# smps_schematic.net
KiCad netlist of a schematic drawn in EAGLE
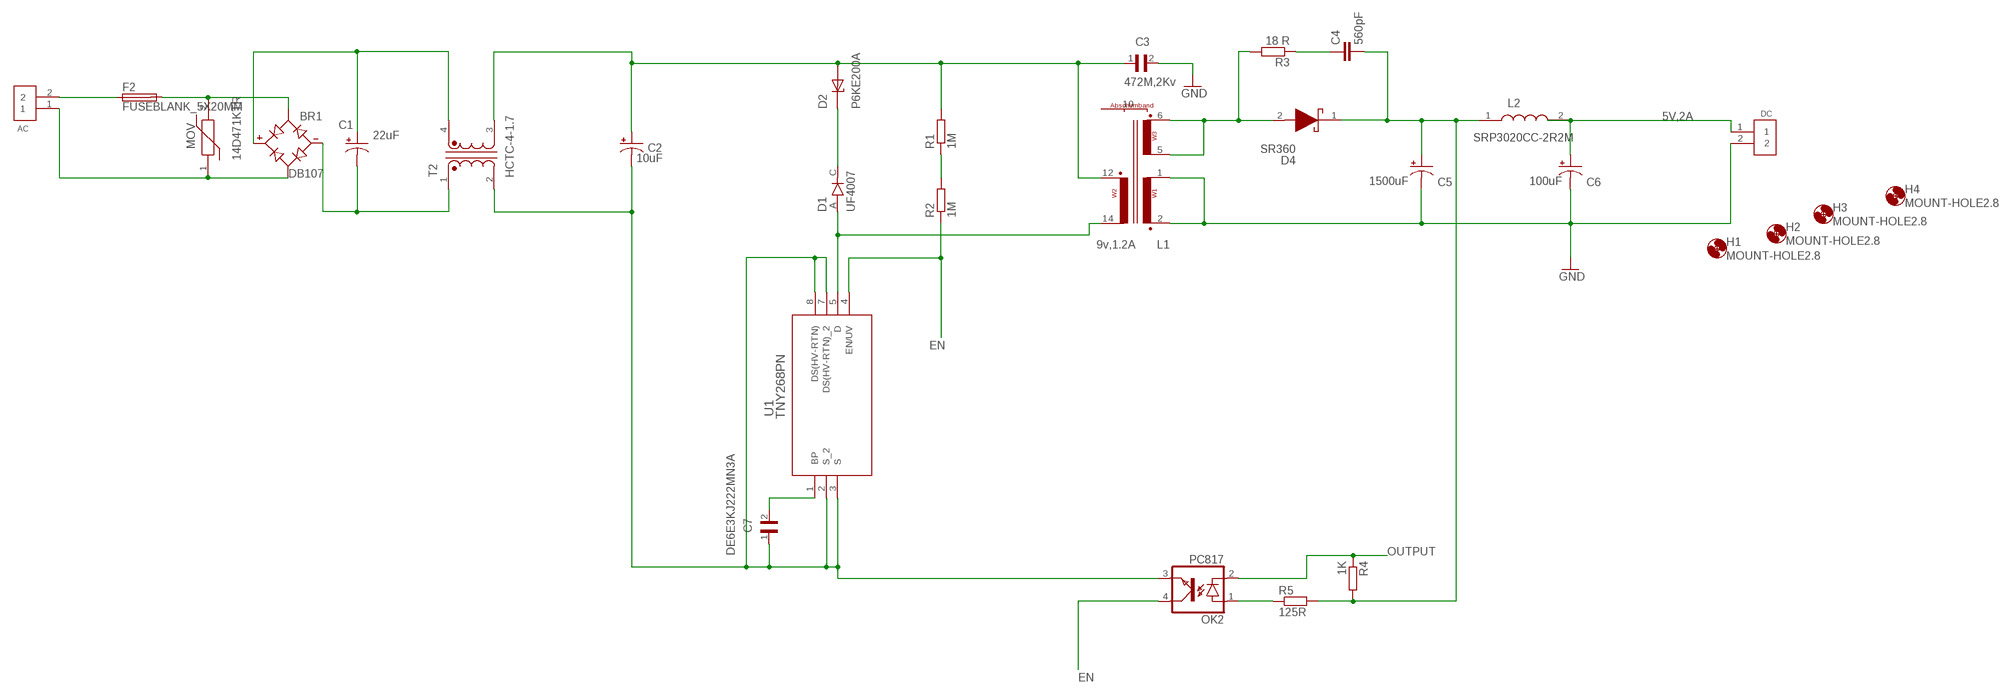
[diagram p0: schematic, sheet 1]

(export (version "E")
  (design (tool "Eeschema 10.0.6"))
  (components
    (comp (ref "AC")
      (value "282837-2")
      (footprint "eagle-import:TE_282837-2")
      (fields (field (name "MF") "TE Connectivity"))
      (libsource (lib "eagle-import") (part "282837-2"))
    )
    (comp (ref "BR1")
      (value "DB107")
      (footprint "eagle-import:DIP825W50P509L880H320Q4")
      (fields (field (name "MF") "Rectron USA"))
      (libsource (lib "eagle-import") (part "DB107"))
    )
    (comp (ref "C1")
      (value "22uF")
      (footprint "eagle-import:CPOL-RADIAL-1F-2.7V")
      (libsource (lib "eagle-import") (part "1F-2.7V(PTH)CPOL-RADIAL-1H-2.7V"))
    )
    (comp (ref "C2")
      (value "10uF")
      (footprint "eagle-import:CPOL-RADIAL-1F-2.7V")
      (libsource (lib "eagle-import") (part "1F-2.7V(PTH)CPOL-RADIAL-1H-2.7V"))
    )
    (comp (ref "C3")
      (value "472M,2Kv")
      (footprint "eagle-import:CAP_DE6E3KJ222MN3A")
      (fields (field (name "MF") "Murata Electronics") (field (name "MP") "DE6E3KJ222MN3A"))
      (libsource (lib "eagle-import") (part "DE6E3KJ222MN3A"))
    )
    (comp (ref "C4")
      (value "560pF")
      (footprint "eagle-import:C2.5-3")
      (libsource (lib "eagle-import") (part "C2,5-3"))
    )
    (comp (ref "C5")
      (value "1500uF")
      (footprint "eagle-import:CPOL-RADIAL-1F-2.7V")
      (libsource (lib "eagle-import") (part "1F-2.7V(PTH)CPOL-RADIAL-1H-2.7V"))
    )
    (comp (ref "C6")
      (value "100uF")
      (footprint "eagle-import:CPOL-RADIAL-1F-2.7V")
      (libsource (lib "eagle-import") (part "1F-2.7V(PTH)CPOL-RADIAL-1H-2.7V"))
    )
    (comp (ref "C7")
      (value "DE6E3KJ222MN3A")
      (footprint "eagle-import:CAP_DE6E3KJ222MN3A")
      (fields (field (name "MF") "Murata Electronics"))
      (libsource (lib "eagle-import") (part "DE6E3KJ222MN3A"))
    )
    (comp (ref "D1")
      (value "UF4007")
      (footprint "eagle-import:DIOAD1036W78L520D274")
      (fields (field (name "MF") "onsemi"))
      (libsource (lib "eagle-import") (part "UF4007"))
    )
    (comp (ref "D2")
      (value "P6KE200A")
      (footprint "eagle-import:DIOAD1276W78L760D360")
      (fields (field (name "MF") "STMicroelectronics"))
      (libsource (lib "eagle-import") (part "P6KE200A"))
    )
    (comp (ref "D4")
      (value "SR360")
      (footprint "eagle-import:DIOAD3020W130L900D530")
      (libsource (lib "eagle-import") (part "SR360"))
    )
    (comp (ref "DC")
      (value "282837-2")
      (footprint "eagle-import:TE_282837-2")
      (fields (field (name "MF") "TE Connectivity"))
      (libsource (lib "eagle-import") (part "282837-2"))
    )
    (comp (ref "F2")
      (value "FUSEBLANK_5X20MM")
      (footprint "eagle-import:FUSE_HOLDER_5X20MM")
      (libsource (lib "eagle-import") (part "FUSEBLANK_5X20MM"))
    )
    (comp (ref "H1")
      (value "MOUNT-HOLE2.8")
      (footprint "eagle-import:2,8")
      (libsource (lib "eagle-import") (part "MOUNT-HOLE2.8"))
    )
    (comp (ref "H2")
      (value "MOUNT-HOLE2.8")
      (footprint "eagle-import:2,8")
      (libsource (lib "eagle-import") (part "MOUNT-HOLE2.8"))
    )
    (comp (ref "H3")
      (value "MOUNT-HOLE2.8")
      (footprint "eagle-import:2,8")
      (libsource (lib "eagle-import") (part "MOUNT-HOLE2.8"))
    )
    (comp (ref "H4")
      (value "MOUNT-HOLE2.8")
      (footprint "eagle-import:2,8")
      (libsource (lib "eagle-import") (part "MOUNT-HOLE2.8"))
    )
    (comp (ref "L1")
      (value "9v,1.2A")
      (footprint "eagle-import:ST-D2")
      (libsource (lib "eagle-import") (part "ST-D2"))
    )
    (comp (ref "L2")
      (value "SRP3020CC-2R2M")
      (footprint "eagle-import:INDPM3532X200N")
      (fields (field (name "MOUSER_PART_NUMBER") "652-SRP3020CC-2R2M"))
      (libsource (lib "eagle-import") (part "SRP3020CC-2R2M"))
    )
    (comp (ref "MOV")
      (value "14D471KTR")
      (footprint "eagle-import:MOV14D471K")
      (fields
        (field (name "ARROW_PART_NUMBER") "MOV-14D471KTR")
        (field (name "MOUSER_PART_NUMBER") "652-MOV-14D471KTR")
      )
      (libsource (lib "eagle-import") (part "MOV-14D471KTR"))
    )
    (comp (ref "OK2")
      (value "PC817")
      (footprint "eagle-import:DIL04")
      (fields (field (name "MPN") "PC817X4J000F"))
      (libsource (lib "eagle-import") (part "PC817"))
    )
    (comp (ref "R1")
      (value "1M")
      (footprint "eagle-import:0204_7")
      (libsource (lib "eagle-import") (part "R-EU_0204/7"))
    )
    (comp (ref "R2")
      (value "1M")
      (footprint "eagle-import:0204_7")
      (libsource (lib "eagle-import") (part "R-EU_0204/7"))
    )
    (comp (ref "R3")
      (value "18 R")
      (footprint "eagle-import:0204_7")
      (libsource (lib "eagle-import") (part "R-EU_0204/7"))
    )
    (comp (ref "R4")
      (value "1K")
      (footprint "eagle-import:0204_7")
      (libsource (lib "eagle-import") (part "R-EU_0204/7"))
    )
    (comp (ref "R5")
      (value "125R")
      (footprint "eagle-import:0204_7")
      (libsource (lib "eagle-import") (part "R-EU_0204/7"))
    )
    (comp (ref "T2")
      (value "HCTC-4-1.7")
      (footprint "eagle-import:XFMR_HCTC-4-1.7")
      (fields (field (name "MF") "Bel Fuse"))
      (libsource (lib "eagle-import") (part "HCTC-4-1.7"))
    )
    (comp (ref "U1")
      (value "TNY268PN")
      (footprint "eagle-import:PDIP-8B_P_PWI")
      (fields (field (name "COPYRIGHT") "Copyright (C) 2024 Ultra Librarian. All rights reserved."))
      (libsource (lib "eagle-import") (part "TNY268PN"))
    )
  )
  (nets
    (net (code "1") (name "/5V,2A") (class "Default")
      (node (ref "C6") (pin "+") (pinfunction "+_+") (pintype "passive"))
      (node (ref "DC") (pin "1") (pinfunction "1_1") (pintype "passive"))
      (node (ref "L2") (pin "2") (pinfunction "2_2") (pintype "bidirectional"))
    )
    (net (code "2") (name "/EN") (class "Default")
      (node (ref "OK2") (pin "4") (pinfunction "COL_4") (pintype "passive"))
      (node (ref "R2") (pin "1") (pinfunction "1_1") (pintype "passive"))
      (node (ref "U1") (pin "4") (pinfunction "EN/UV_4") (pintype "bidirectional"))
    )
    (net (code "3") (name "/OUTPUT") (class "Default")
      (node (ref "OK2") (pin "2") (pinfunction "C_2") (pintype "passive"))
      (node (ref "R4") (pin "1") (pinfunction "1_1") (pintype "passive"))
    )
    (net (code "4") (name "GND") (class "Default")
      (node (ref "C3") (pin "2") (pinfunction "2_2") (pintype "passive"))
      (node (ref "C5") (pin "-") (pinfunction "-_-") (pintype "passive"))
      (node (ref "C6") (pin "-") (pinfunction "-_-") (pintype "passive"))
      (node (ref "DC") (pin "2") (pinfunction "2_2") (pintype "passive"))
      (node (ref "L1") (pin "1") (pinfunction "1E_1") (pintype "passive"))
      (node (ref "L1") (pin "2") (pinfunction "1A_2") (pintype "passive"))
    )
    (net (code "5") (name "Net-(AC-Pad2)") (class "Default")
      (node (ref "AC") (pin "2") (pinfunction "2_2") (pintype "passive"))
      (node (ref "F2") (pin "1") (pinfunction "1_1") (pintype "passive"))
    )
    (net (code "6") (name "Net-(BR1-+)") (class "Default")
      (node (ref "BR1") (pin "1") (pinfunction "+_1") (pintype "passive"))
      (node (ref "C1") (pin "+") (pinfunction "+_+") (pintype "passive"))
      (node (ref "T2") (pin "4") (pinfunction "4_4") (pintype "passive"))
    )
    (net (code "7") (name "Net-(BR1--)") (class "Default")
      (node (ref "BR1") (pin "2") (pinfunction "-_2") (pintype "passive"))
      (node (ref "C1") (pin "-") (pinfunction "-_-") (pintype "passive"))
      (node (ref "T2") (pin "1") (pinfunction "1_1") (pintype "passive"))
    )
    (net (code "8") (name "Net-(BR1-AC1)") (class "Default")
      (node (ref "BR1") (pin "3") (pinfunction "AC1_3") (pintype "passive"))
      (node (ref "F2") (pin "2") (pinfunction "2_2") (pintype "passive"))
      (node (ref "MOV") (pin "2") (pinfunction "2_2") (pintype "bidirectional"))
    )
    (net (code "9") (name "Net-(BR1-AC2)") (class "Default")
      (node (ref "AC") (pin "1") (pinfunction "1_1") (pintype "passive"))
      (node (ref "BR1") (pin "4") (pinfunction "AC2_4") (pintype "passive"))
      (node (ref "MOV") (pin "1") (pinfunction "1_1") (pintype "bidirectional"))
    )
    (net (code "10") (name "Net-(C4-Pad1)") (class "Default")
      (node (ref "C4") (pin "1") (pinfunction "1_1") (pintype "passive"))
      (node (ref "R3") (pin "1") (pinfunction "1_1") (pintype "passive"))
    )
    (net (code "11") (name "Net-(D1-K)") (class "Default")
      (node (ref "D1") (pin "C") (pinfunction "K_C") (pintype "passive"))
      (node (ref "D2") (pin "C") (pinfunction "C_C") (pintype "passive"))
    )
    (net (code "12") (name "Net-(D4-A)") (class "Default")
      (node (ref "D4") (pin "2") (pinfunction "A_2") (pintype "bidirectional"))
      (node (ref "L1") (pin "5") (pinfunction "3E_5") (pintype "passive"))
      (node (ref "L1") (pin "6") (pinfunction "3A_6") (pintype "passive"))
      (node (ref "R3") (pin "2") (pinfunction "2_2") (pintype "passive"))
    )
    (net (code "13") (name "Net-(D4-K)") (class "Default")
      (node (ref "C4") (pin "2") (pinfunction "2_2") (pintype "passive"))
      (node (ref "C5") (pin "+") (pinfunction "+_+") (pintype "passive"))
      (node (ref "D4") (pin "1") (pinfunction "K_1") (pintype "bidirectional"))
      (node (ref "L2") (pin "1") (pinfunction "1_1") (pintype "bidirectional"))
      (node (ref "R4") (pin "2") (pinfunction "2_2") (pintype "passive"))
      (node (ref "R5") (pin "2") (pinfunction "2_2") (pintype "passive"))
    )
    (net (code "14") (name "Net-(L1-2A)") (class "Default")
      (node (ref "C2") (pin "+") (pinfunction "+_+") (pintype "passive"))
      (node (ref "C3") (pin "1") (pinfunction "1_1") (pintype "passive"))
      (node (ref "D2") (pin "A") (pinfunction "A_A") (pintype "passive"))
      (node (ref "L1") (pin "12") (pinfunction "2A_12") (pintype "passive"))
      (node (ref "R1") (pin "2") (pinfunction "2_2") (pintype "passive"))
      (node (ref "T2") (pin "3") (pinfunction "3_3") (pintype "passive"))
    )
    (net (code "15") (name "Net-(L1-2E)") (class "Default")
      (node (ref "D1") (pin "A") (pinfunction "A_A") (pintype "passive"))
      (node (ref "L1") (pin "14") (pinfunction "2E_14") (pintype "passive"))
      (node (ref "U1") (pin "5") (pinfunction "D_5") (pintype "output"))
    )
    (net (code "16") (name "Net-(OK2-A)") (class "Default")
      (node (ref "OK2") (pin "1") (pinfunction "A_1") (pintype "passive"))
      (node (ref "R5") (pin "1") (pinfunction "1_1") (pintype "passive"))
    )
    (net (code "17") (name "Net-(OK2-EMIT)") (class "Default")
      (node (ref "C2") (pin "-") (pinfunction "-_-") (pintype "passive"))
      (node (ref "C7") (pin "1") (pinfunction "1_1") (pintype "passive"))
      (node (ref "OK2") (pin "3") (pinfunction "EMIT_3") (pintype "passive"))
      (node (ref "T2") (pin "2") (pinfunction "2_2") (pintype "passive"))
      (node (ref "U1") (pin "2") (pinfunction "S_2_2") (pintype "power_in"))
      (node (ref "U1") (pin "3") (pinfunction "S_3") (pintype "power_in"))
      (node (ref "U1") (pin "7") (pinfunction "DS(HV-RTN)_2_7") (pintype "power_in"))
      (node (ref "U1") (pin "8") (pinfunction "DS(HV-RTN)_8") (pintype "power_in"))
    )
    (net (code "18") (name "Net-(R1-Pad1)") (class "Default")
      (node (ref "R1") (pin "1") (pinfunction "1_1") (pintype "passive"))
      (node (ref "R2") (pin "2") (pinfunction "2_2") (pintype "passive"))
    )
    (net (code "19") (name "Net-(U1-BP)") (class "Default")
      (node (ref "C7") (pin "2") (pinfunction "2_2") (pintype "passive"))
      (node (ref "U1") (pin "1") (pinfunction "BP_1") (pintype "passive"))
    )
    (net (code "20") (name "unconnected-(L1-SCH-Pad10)") (class "Default")
      (node (ref "L1") (pin "10") (pinfunction "SCH_10") (pintype "passive"))
    )
    (net (code "21") (name "unconnected-(L1-SCH1-Pad13)") (class "Default")
      (node (ref "L1") (pin "13") (pinfunction "SCH1_13") (pintype "passive"))
    )
  )
)
